# AVR.net
KiCad netlist of a schematic drawn in EAGLE
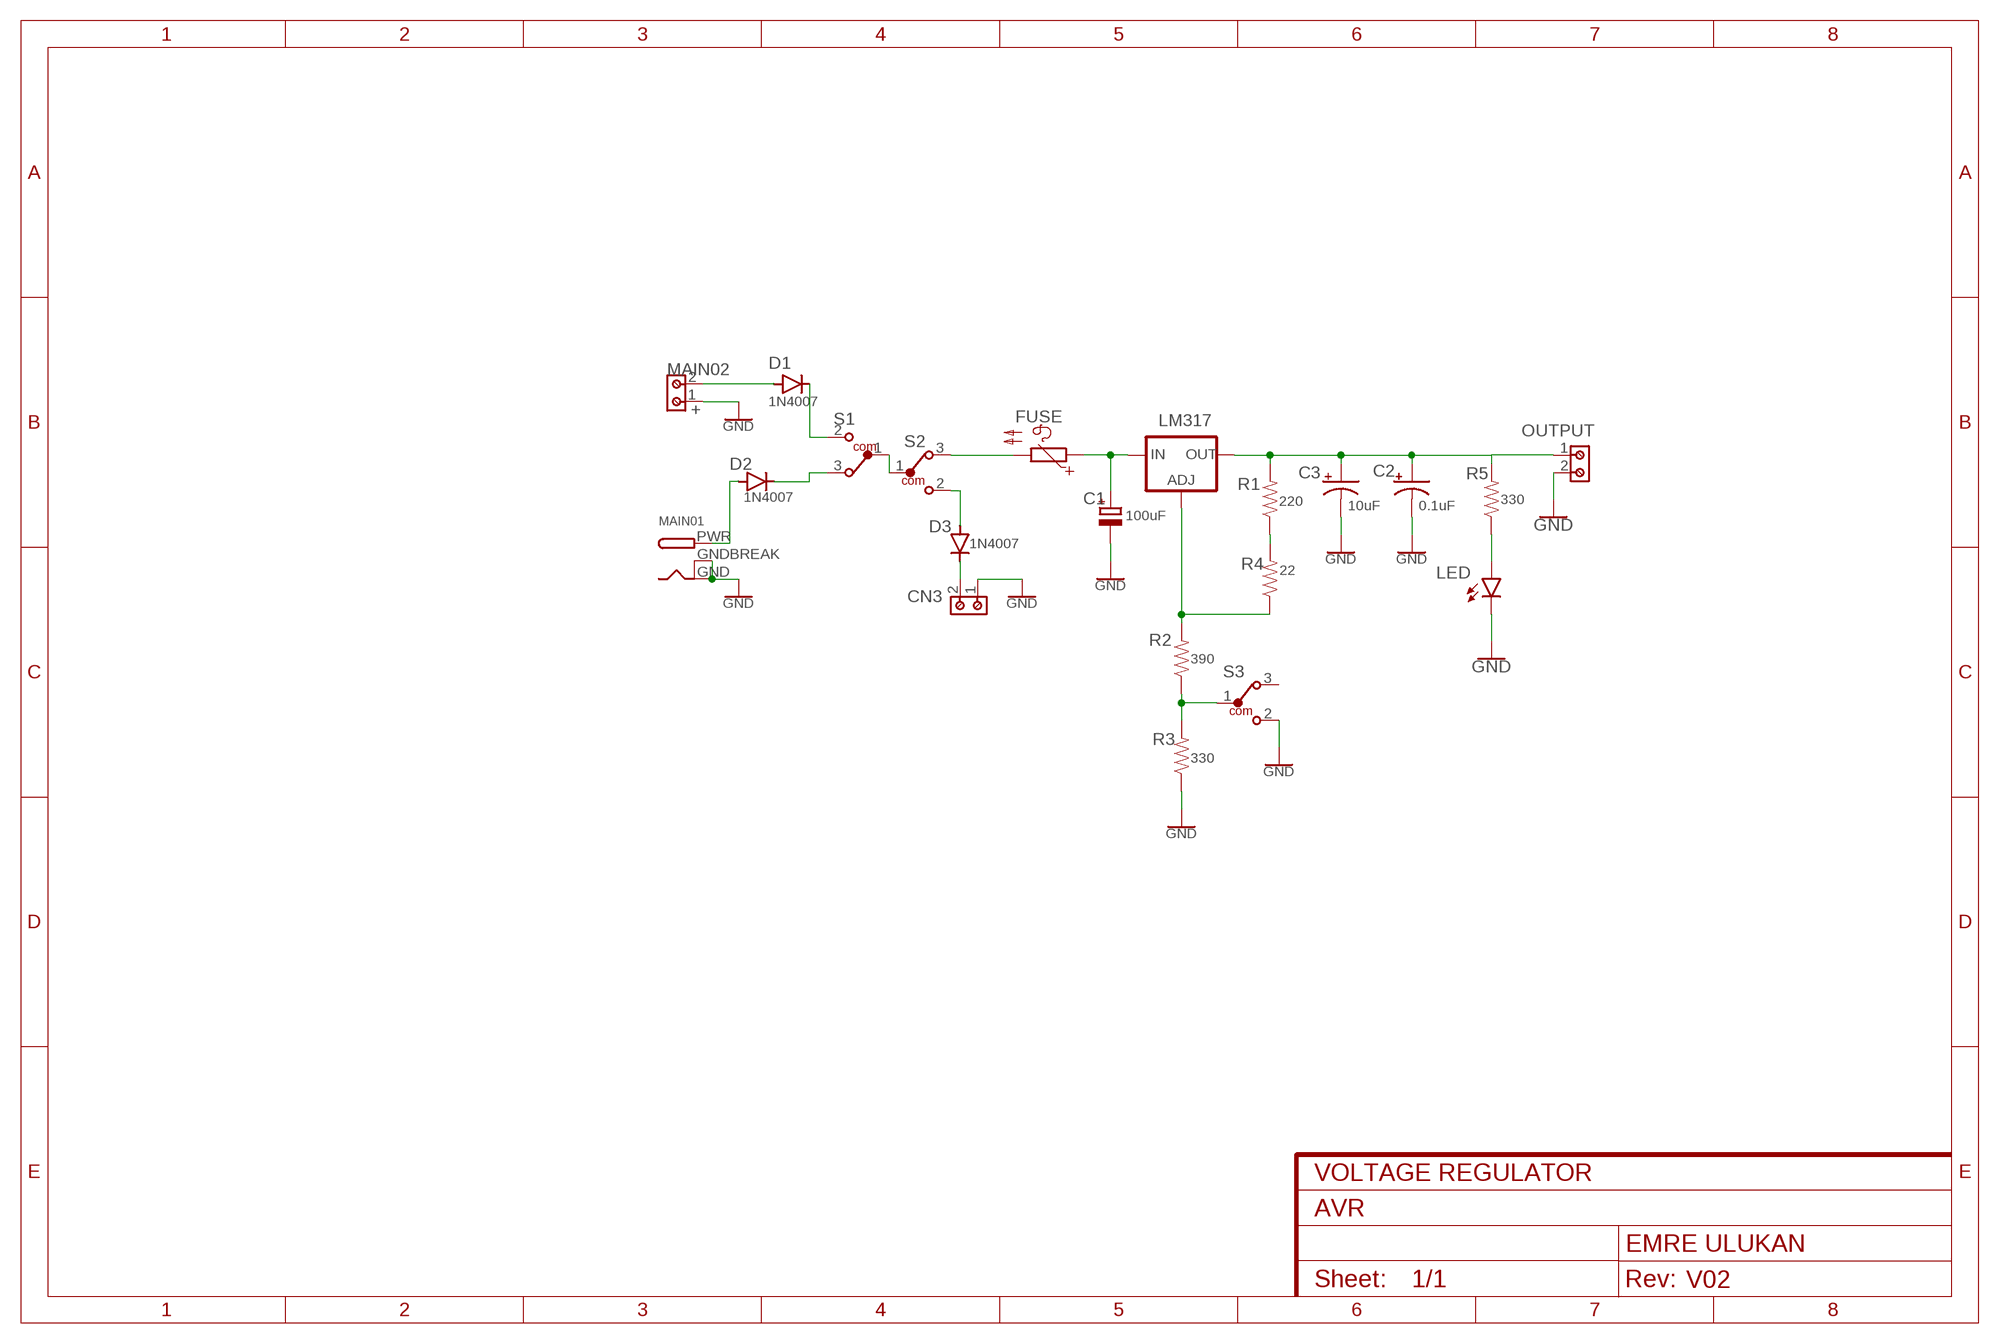
[diagram p0: schematic, sheet 1]

(export (version "E")
  (design (tool "Eeschema 10.0.6"))
  (components
    (comp (ref "C1")
      (value "100uF")
      (footprint "eagle-import:E2-5")
      (libsource (lib "eagle-import") (part "CPOL-EUE2-5"))
    )
    (comp (ref "C2")
      (value "0.1uF")
      (footprint "eagle-import:E2,5-5")
      (libsource (lib "eagle-import") (part "CAPACITOR-PE2.5-5"))
    )
    (comp (ref "C3")
      (value "10uF")
      (footprint "eagle-import:E2,5-5")
      (libsource (lib "eagle-import") (part "CAPACITOR-PE2.5-5"))
    )
    (comp (ref "CN3")
      (value "691211720002")
      (footprint "eagle-import:691211720002")
      (libsource (lib "eagle-import") (part "691211720002"))
    )
    (comp (ref "D1")
      (value "1N4007")
      (footprint "eagle-import:DO-41")
      (fields
        (field (name "DIGIKEY_PART_NUMBER") "1N4004MSCT-ND")
        (field (name "MANUFACTURER") "Micro Commercial Co")
        (field (name "MPN") "1N4004")
        (field (name "CREATED_BY") "PCBLayout.com")
      )
      (libsource (lib "eagle-import") (part "1N4004"))
    )
    (comp (ref "D2")
      (value "1N4007")
      (footprint "eagle-import:DO-41")
      (fields
        (field (name "DIGIKEY_PART_NUMBER") "1N4004MSCT-ND")
        (field (name "MANUFACTURER") "Micro Commercial Co")
        (field (name "MPN") "1N4004")
        (field (name "CREATED_BY") "PCBLayout.com")
      )
      (libsource (lib "eagle-import") (part "1N4004"))
    )
    (comp (ref "D3")
      (value "1N4007")
      (footprint "eagle-import:DO-41")
      (fields
        (field (name "DIGIKEY_PART_NUMBER") "1N4004MSCT-ND")
        (field (name "MANUFACTURER") "Micro Commercial Co")
        (field (name "MPN") "1N4004")
        (field (name "CREATED_BY") "PCBLayout.com")
      )
      (libsource (lib "eagle-import") (part "1N4004"))
    )
    (comp (ref "FUSE")
      (value "PTC660")
      (footprint "eagle-import:P660")
      (libsource (lib "eagle-import") (part "PTC660"))
    )
    (comp (ref "LED")
      (value "LED3MM")
      (footprint "eagle-import:LED_3MM")
      (libsource (lib "eagle-import") (part "LED3MM"))
    )
    (comp (ref "LM317")
      (value "LM317")
      (footprint "eagle-import:TO220-ADJ")
      (libsource (lib "eagle-import") (part "V_REG_317SINK"))
    )
    (comp (ref "MAIN01")
      (value "DCBARRELPTH")
      (footprint "eagle-import:DCJACK_2MM_PTH")
      (libsource (lib "eagle-import") (part "DCBARRELPTH"))
    )
    (comp (ref "MAIN02")
      (value "691211720002")
      (footprint "eagle-import:691211720002")
      (libsource (lib "eagle-import") (part "691211720002"))
    )
    (comp (ref "OUTPUT")
      (value "691211720002")
      (footprint "eagle-import:691211720002")
      (libsource (lib "eagle-import") (part "691211720002"))
    )
    (comp (ref "R1")
      (value "220")
      (footprint "eagle-import:AXIAL-0.3")
      (libsource (lib "eagle-import") (part "1KOHM-HORIZ-1/4W-5%"))
    )
    (comp (ref "R2")
      (value "390")
      (footprint "eagle-import:AXIAL-0.3")
      (libsource (lib "eagle-import") (part "1KOHM-HORIZ-1/4W-5%"))
    )
    (comp (ref "R3")
      (value "330")
      (footprint "eagle-import:AXIAL-0.3")
      (libsource (lib "eagle-import") (part "1KOHM-HORIZ-1/4W-5%"))
    )
    (comp (ref "R4")
      (value "22")
      (footprint "eagle-import:AXIAL-0.3")
      (libsource (lib "eagle-import") (part "1KOHM-HORIZ-1/4W-5%"))
    )
    (comp (ref "R5")
      (value "330")
      (footprint "eagle-import:AXIAL-0.3")
      (libsource (lib "eagle-import") (part "1KOHM-HORIZ-1/4W-5%"))
    )
    (comp (ref "S1")
      (value "450301014042")
      (footprint "eagle-import:450301014042")
      (libsource (lib "eagle-import") (part "450301014042"))
    )
    (comp (ref "S2")
      (value "450301014042")
      (footprint "eagle-import:450301014042")
      (libsource (lib "eagle-import") (part "450301014042"))
    )
    (comp (ref "S3")
      (value "450301014042")
      (footprint "eagle-import:450301014042")
      (libsource (lib "eagle-import") (part "450301014042"))
    )
  )
  (nets
    (net (code "1") (name "GND") (class "Default")
      (node (ref "C1") (pin "-") (pinfunction "-_-") (pintype "passive"))
      (node (ref "C2") (pin "-") (pinfunction "-_-") (pintype "passive"))
      (node (ref "C3") (pin "-") (pinfunction "-_-") (pintype "passive"))
      (node (ref "CN3") (pin "1") (pinfunction "1_1") (pintype "passive"))
      (node (ref "LED") (pin "K") (pinfunction "C_K") (pintype "passive"))
      (node (ref "MAIN01") (pin "GND") (pinfunction "GND_GND") (pintype "power_in"))
      (node (ref "MAIN01") (pin "GNDBREAK") (pinfunction "GNDBREAK_GNDBREAK") (pintype "power_in"))
      (node (ref "MAIN02") (pin "1") (pinfunction "1_1") (pintype "passive"))
      (node (ref "OUTPUT") (pin "2") (pinfunction "2_2") (pintype "passive"))
      (node (ref "R3") (pin "P$1") (pinfunction "1_P$1") (pintype "passive"))
      (node (ref "S3") (pin "2") (pinfunction "2_2") (pintype "passive"))
    )
    (net (code "2") (name "Net-(C1-Pad+)") (class "Default")
      (node (ref "C1") (pin "+") (pinfunction "+_+") (pintype "passive"))
      (node (ref "FUSE") (pin "1") (pinfunction "1_1") (pintype "passive"))
      (node (ref "LM317") (pin "IN") (pinfunction "IN_IN") (pintype "input"))
    )
    (net (code "3") (name "Net-(CN3-Pad2)") (class "Default")
      (node (ref "CN3") (pin "2") (pinfunction "2_2") (pintype "passive"))
      (node (ref "D3") (pin "C") (pinfunction "C_C") (pintype "passive"))
    )
    (net (code "4") (name "Net-(D1-PadA)") (class "Default")
      (node (ref "D1") (pin "A") (pinfunction "A_A") (pintype "passive"))
      (node (ref "MAIN02") (pin "2") (pinfunction "2_2") (pintype "passive"))
    )
    (net (code "5") (name "Net-(D1-PadC)") (class "Default")
      (node (ref "D1") (pin "C") (pinfunction "C_C") (pintype "passive"))
      (node (ref "S1") (pin "2") (pinfunction "2_2") (pintype "passive"))
    )
    (net (code "6") (name "Net-(D2-PadA)") (class "Default")
      (node (ref "D2") (pin "A") (pinfunction "A_A") (pintype "passive"))
      (node (ref "MAIN01") (pin "PWR") (pinfunction "PWR_PWR") (pintype "power_in"))
    )
    (net (code "7") (name "Net-(D2-PadC)") (class "Default")
      (node (ref "D2") (pin "C") (pinfunction "C_C") (pintype "passive"))
      (node (ref "S1") (pin "3") (pinfunction "3_3") (pintype "passive"))
    )
    (net (code "8") (name "Net-(D3-PadA)") (class "Default")
      (node (ref "D3") (pin "A") (pinfunction "A_A") (pintype "passive"))
      (node (ref "S2") (pin "2") (pinfunction "2_2") (pintype "passive"))
    )
    (net (code "9") (name "Net-(FUSE-Pad2)") (class "Default")
      (node (ref "FUSE") (pin "2") (pinfunction "2_2") (pintype "passive"))
      (node (ref "S2") (pin "3") (pinfunction "3_3") (pintype "passive"))
    )
    (net (code "10") (name "Net-(R1-1)") (class "Default")
      (node (ref "R1") (pin "P$1") (pinfunction "1_P$1") (pintype "passive"))
      (node (ref "R4") (pin "P$2") (pinfunction "2_P$2") (pintype "passive"))
    )
    (net (code "11") (name "Net-(R1-2)") (class "Default")
      (node (ref "C2") (pin "+") (pinfunction "+_+") (pintype "passive"))
      (node (ref "C3") (pin "+") (pinfunction "+_+") (pintype "passive"))
      (node (ref "LM317") (pin "OUT") (pinfunction "OUT_OUT") (pintype "output"))
      (node (ref "OUTPUT") (pin "1") (pinfunction "1_1") (pintype "passive"))
      (node (ref "R1") (pin "P$2") (pinfunction "2_P$2") (pintype "passive"))
      (node (ref "R5") (pin "P$2") (pinfunction "2_P$2") (pintype "passive"))
    )
    (net (code "12") (name "Net-(R2-1)") (class "Default")
      (node (ref "R2") (pin "P$1") (pinfunction "1_P$1") (pintype "passive"))
      (node (ref "R3") (pin "P$2") (pinfunction "2_P$2") (pintype "passive"))
      (node (ref "S3") (pin "1") (pinfunction "1_1") (pintype "passive"))
    )
    (net (code "13") (name "Net-(R2-2)") (class "Default")
      (node (ref "LM317") (pin "ADJ") (pinfunction "ADJ_ADJ") (pintype "input"))
      (node (ref "R2") (pin "P$2") (pinfunction "2_P$2") (pintype "passive"))
      (node (ref "R4") (pin "P$1") (pinfunction "1_P$1") (pintype "passive"))
    )
    (net (code "14") (name "Net-(R5-1)") (class "Default")
      (node (ref "LED") (pin "A") (pinfunction "A_A") (pintype "passive"))
      (node (ref "R5") (pin "P$1") (pinfunction "1_P$1") (pintype "passive"))
    )
    (net (code "15") (name "Net-(S1-Pad1)") (class "Default")
      (node (ref "S1") (pin "1") (pinfunction "1_1") (pintype "passive"))
      (node (ref "S2") (pin "1") (pinfunction "1_1") (pintype "passive"))
    )
    (net (code "16") (name "unconnected-(S3-Pad3)") (class "Default")
      (node (ref "S3") (pin "3") (pinfunction "3_3") (pintype "passive"))
    )
  )
)
